# Microcontroller_Power.net
KiCad netlist of a schematic drawn in Altium Designer
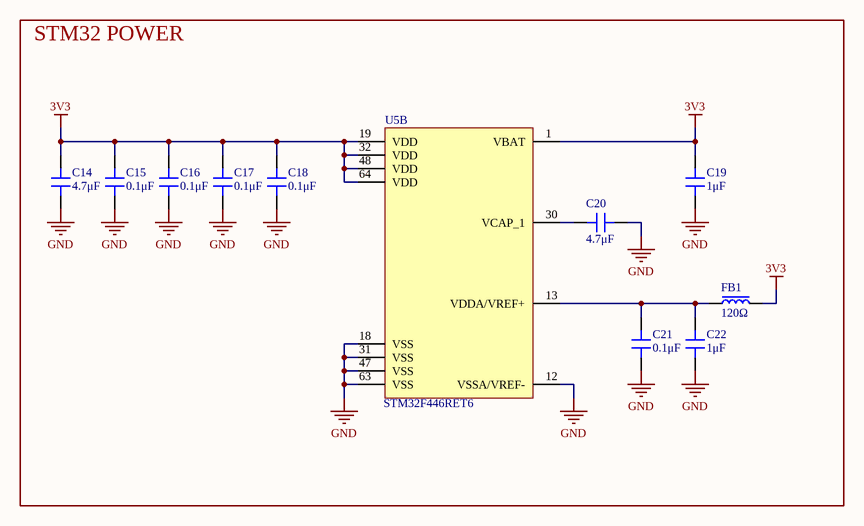
[diagram p0: Microcontroller Power.SchDoc]

(export (version "E")
  (design (tool "Eeschema 10.0.6"))
  (components
    (comp (ref "C14")
      (value "4.7μF")
      (footprint "C0805")
      (description "16V 4.7uF X7R ±10% 0805 Multilayer Ceramic Capacitors MLCC - SMD/SMT ROHS")
      (fields
        (field (name "MANUFACTURER") "Taiyo Yuden")
        (field (name "MANUFACTURER PART NUMBER") "EMK212B7475KG-T")
      )
      (libsource (lib "REFLOW_CONTROLLER") (part "C-4.7UF-16V-X7R-C0805"))
    )
    (comp (ref "C15")
      (value "0.1μF")
      (footprint "C0603")
      (description "50V 100nF X7R ±10% 0603 Multilayer Ceramic Capacitors MLCC - SMD/SMT ROHS")
      (fields
        (field (name "MANUFACTURER") "Samsung Electro-Mechanics")
        (field (name "MANUFACTURER PART NUMBER") "CL10B104KB8NNNC")
      )
      (libsource (lib "REFLOW_CONTROLLER") (part "C-0.1UF-50V-X7R-C0603"))
    )
    (comp (ref "C16")
      (value "0.1μF")
      (footprint "C0603")
      (description "50V 100nF X7R ±10% 0603 Multilayer Ceramic Capacitors MLCC - SMD/SMT ROHS")
      (fields
        (field (name "MANUFACTURER") "Samsung Electro-Mechanics")
        (field (name "MANUFACTURER PART NUMBER") "CL10B104KB8NNNC")
      )
      (libsource (lib "REFLOW_CONTROLLER") (part "C-0.1UF-50V-X7R-C0603"))
    )
    (comp (ref "C17")
      (value "0.1μF")
      (footprint "C0603")
      (description "50V 100nF X7R ±10% 0603 Multilayer Ceramic Capacitors MLCC - SMD/SMT ROHS")
      (fields
        (field (name "MANUFACTURER") "Samsung Electro-Mechanics")
        (field (name "MANUFACTURER PART NUMBER") "CL10B104KB8NNNC")
      )
      (libsource (lib "REFLOW_CONTROLLER") (part "C-0.1UF-50V-X7R-C0603"))
    )
    (comp (ref "C18")
      (value "0.1μF")
      (footprint "C0603")
      (description "50V 100nF X7R ±10% 0603 Multilayer Ceramic Capacitors MLCC - SMD/SMT ROHS")
      (fields
        (field (name "MANUFACTURER") "Samsung Electro-Mechanics")
        (field (name "MANUFACTURER PART NUMBER") "CL10B104KB8NNNC")
      )
      (libsource (lib "REFLOW_CONTROLLER") (part "C-0.1UF-50V-X7R-C0603"))
    )
    (comp (ref "C19")
      (value "1μF")
      (footprint "C0603")
      (description "16V 1uF X7R ±10% 0603 Multilayer Ceramic Capacitors MLCC - SMD/SMT ROHS")
      (fields
        (field (name "MANUFACTURER") "Samsung Electro-Mechanics")
        (field (name "MANUFACTURER PART NUMBER") "CL10B105KO8NNNC")
      )
      (libsource (lib "REFLOW_CONTROLLER") (part "C-1UF-16V-X7R-C0603"))
    )
    (comp (ref "C20")
      (value "4.7μF")
      (footprint "C0805")
      (description "16V 4.7uF X7R ±10% 0805 Multilayer Ceramic Capacitors MLCC - SMD/SMT ROHS")
      (fields
        (field (name "MANUFACTURER") "Taiyo Yuden")
        (field (name "MANUFACTURER PART NUMBER") "EMK212B7475KG-T")
      )
      (libsource (lib "REFLOW_CONTROLLER") (part "C-4.7UF-16V-X7R-C0805"))
    )
    (comp (ref "C21")
      (value "0.1μF")
      (footprint "C0603")
      (description "50V 100nF X7R ±10% 0603 Multilayer Ceramic Capacitors MLCC - SMD/SMT ROHS")
      (fields
        (field (name "MANUFACTURER") "Samsung Electro-Mechanics")
        (field (name "MANUFACTURER PART NUMBER") "CL10B104KB8NNNC")
      )
      (libsource (lib "REFLOW_CONTROLLER") (part "C-0.1UF-50V-X7R-C0603"))
    )
    (comp (ref "C22")
      (value "1μF")
      (footprint "C0603")
      (description "16V 1uF X7R ±10% 0603 Multilayer Ceramic Capacitors MLCC - SMD/SMT ROHS")
      (fields
        (field (name "MANUFACTURER") "Samsung Electro-Mechanics")
        (field (name "MANUFACTURER PART NUMBER") "CL10B105KO8NNNC")
      )
      (libsource (lib "REFLOW_CONTROLLER") (part "C-1UF-16V-X7R-C0603"))
    )
    (comp (ref "FB1")
      (value "120Ω")
      (footprint "FB0603")
      (description "50mΩ ±25% 120Ω@100MHz 0603 Ferrite Beads ROHS")
      (fields
        (field (name "MANUFACTURER") "Murata Electronics")
        (field (name "MANUFACTURER PART NUMBER") "BLM18PG121SN1D")
      )
      (libsource (lib "REFLOW_CONTROLLER") (part "FB-120OHM-50MOHM-FB0603"))
    )
    (comp (ref "U5")
      (value "STM32F446RET6")
      (footprint "LQFP-64_10X10")
      (description "35A 1V@400mA 800mA 600V MBS Bridge Rectifiers ROHS")
      (fields (field (name "MANUFACTURER") "STMicroelectronics"))
      (libsource (lib "REFLOW_CONTROLLER") (part "U-STM32F446RET6-LQFP-64_10X10"))
    )
  )
  (nets
    (net (code "1") (name "3V3") (class "Default")
      (node (ref "C14") (pin "2") (pinfunction "2_2") (pintype "passive"))
      (node (ref "C15") (pin "2") (pinfunction "2_2") (pintype "passive"))
      (node (ref "C16") (pin "2") (pinfunction "2_2") (pintype "passive"))
      (node (ref "C17") (pin "2") (pinfunction "2_2") (pintype "passive"))
      (node (ref "C18") (pin "2") (pinfunction "2_2") (pintype "passive"))
      (node (ref "C19") (pin "2") (pinfunction "2_2") (pintype "passive"))
      (node (ref "FB1") (pin "2") (pinfunction "2_2") (pintype "passive"))
      (node (ref "U5") (pin "1") (pinfunction "VBAT_1") (pintype "passive"))
      (node (ref "U5") (pin "19") (pinfunction "VDD_19") (pintype "passive"))
      (node (ref "U5") (pin "32") (pinfunction "VDD_32") (pintype "passive"))
      (node (ref "U5") (pin "48") (pinfunction "VDD_48") (pintype "passive"))
      (node (ref "U5") (pin "64") (pinfunction "VDD_64") (pintype "passive"))
    )
    (net (code "2") (name "GND") (class "Default")
      (node (ref "C14") (pin "1") (pinfunction "1_1") (pintype "passive"))
      (node (ref "C15") (pin "1") (pinfunction "1_1") (pintype "passive"))
      (node (ref "C16") (pin "1") (pinfunction "1_1") (pintype "passive"))
      (node (ref "C17") (pin "1") (pinfunction "1_1") (pintype "passive"))
      (node (ref "C18") (pin "1") (pinfunction "1_1") (pintype "passive"))
      (node (ref "C19") (pin "1") (pinfunction "1_1") (pintype "passive"))
      (node (ref "C20") (pin "1") (pinfunction "1_1") (pintype "passive"))
      (node (ref "C21") (pin "1") (pinfunction "1_1") (pintype "passive"))
      (node (ref "C22") (pin "1") (pinfunction "1_1") (pintype "passive"))
      (node (ref "U5") (pin "12") (pinfunction "VSSA/VREF-_12") (pintype "passive"))
      (node (ref "U5") (pin "18") (pinfunction "VSS_18") (pintype "passive"))
      (node (ref "U5") (pin "31") (pinfunction "VSS_31") (pintype "passive"))
      (node (ref "U5") (pin "47") (pinfunction "VSS_47") (pintype "passive"))
      (node (ref "U5") (pin "63") (pinfunction "VSS_63") (pintype "passive"))
    )
    (net (code "3") (name "Net-(U5B-VCAP_1)") (class "Default")
      (node (ref "C20") (pin "2") (pinfunction "2_2") (pintype "passive"))
      (node (ref "U5") (pin "30") (pinfunction "VCAP_1_30") (pintype "passive"))
    )
    (net (code "4") (name "Net-(U5B-VDDA{slash}VREF+)") (class "Default")
      (node (ref "C21") (pin "2") (pinfunction "2_2") (pintype "passive"))
      (node (ref "C22") (pin "2") (pinfunction "2_2") (pintype "passive"))
      (node (ref "FB1") (pin "1") (pinfunction "1_1") (pintype "passive"))
      (node (ref "U5") (pin "13") (pinfunction "VDDA/VREF+_13") (pintype "passive"))
    )
  )
)
